# Main.net
KiCad netlist of a schematic drawn in EAGLE
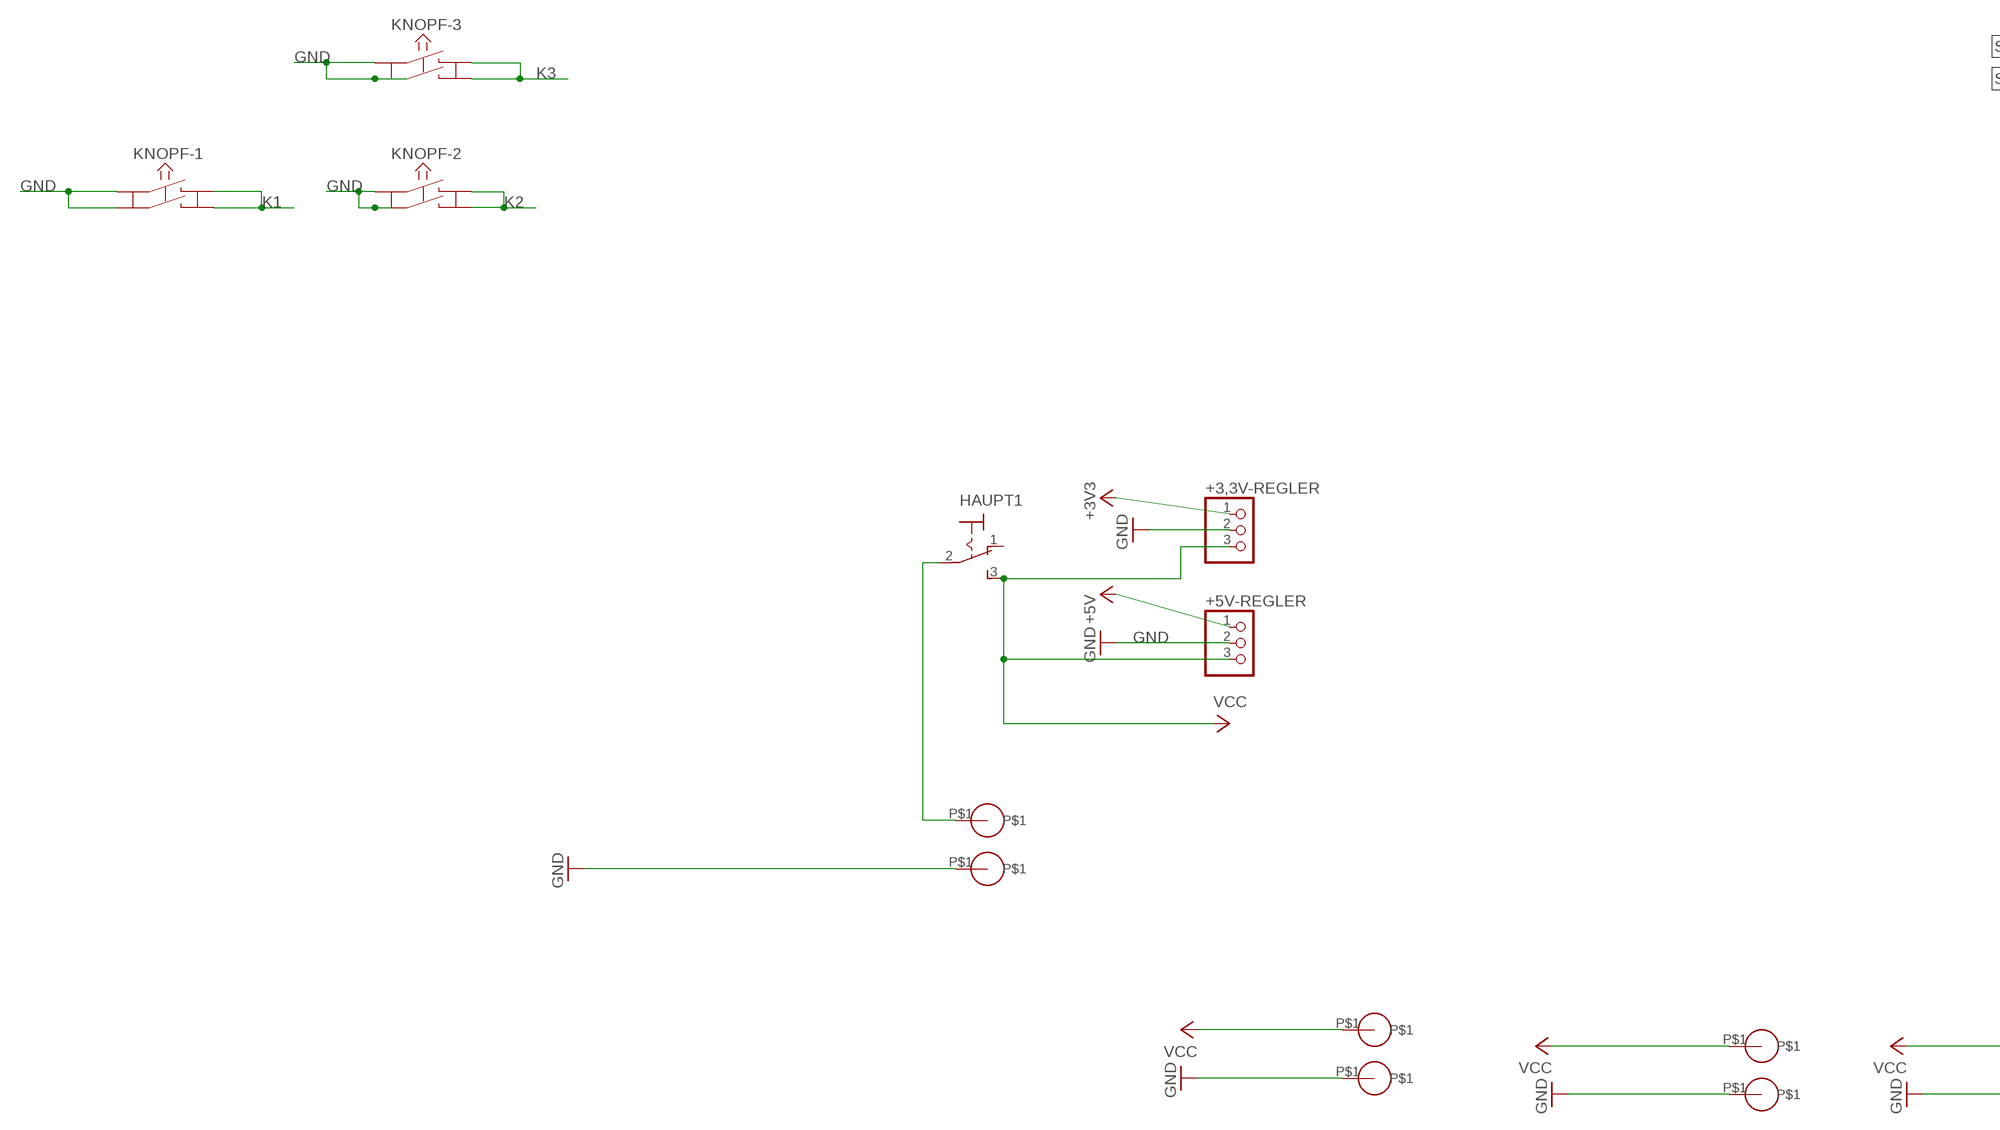
[diagram p0: schematic, sheet 1, part 1 of 3]
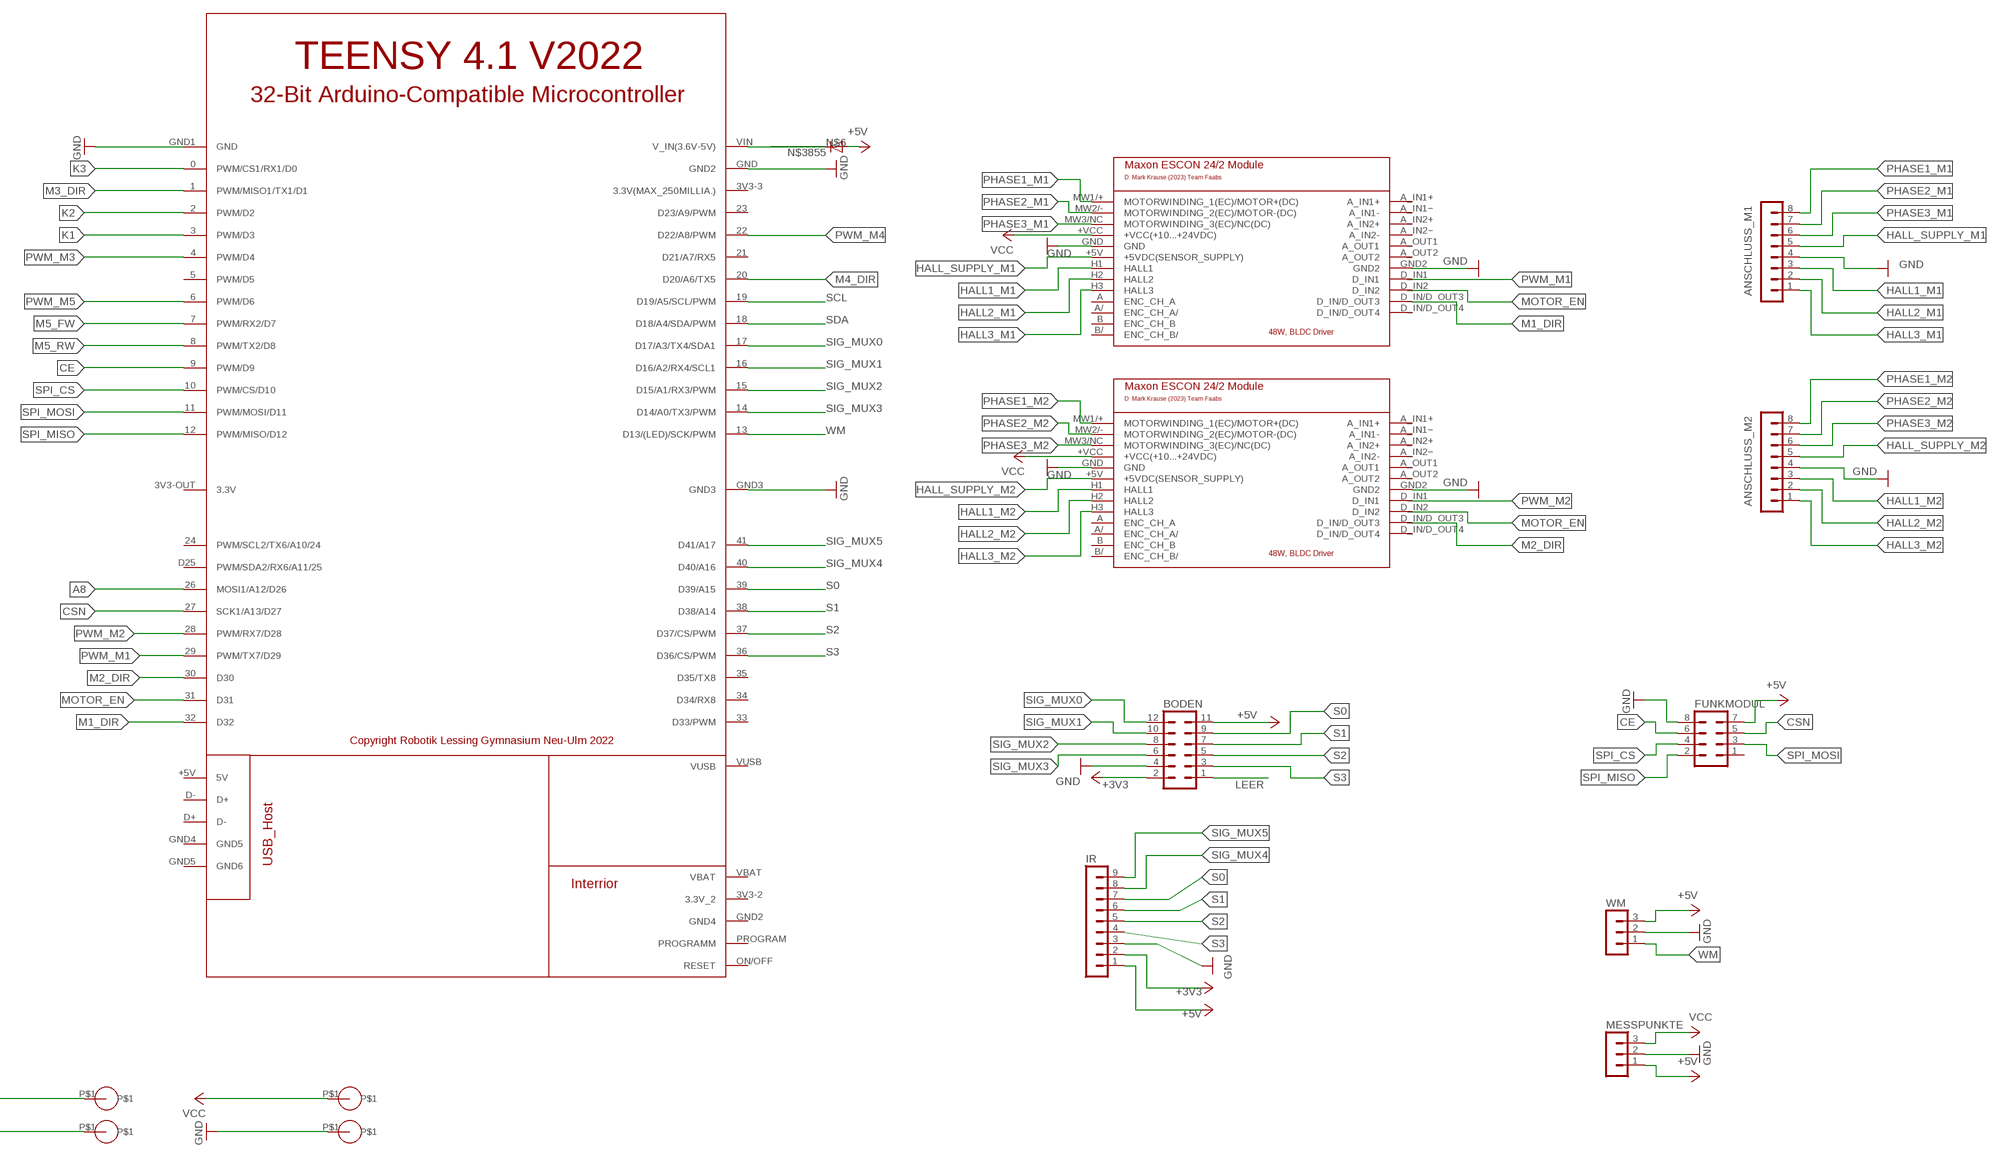
[diagram p1: schematic, sheet 1, part 2 of 3]
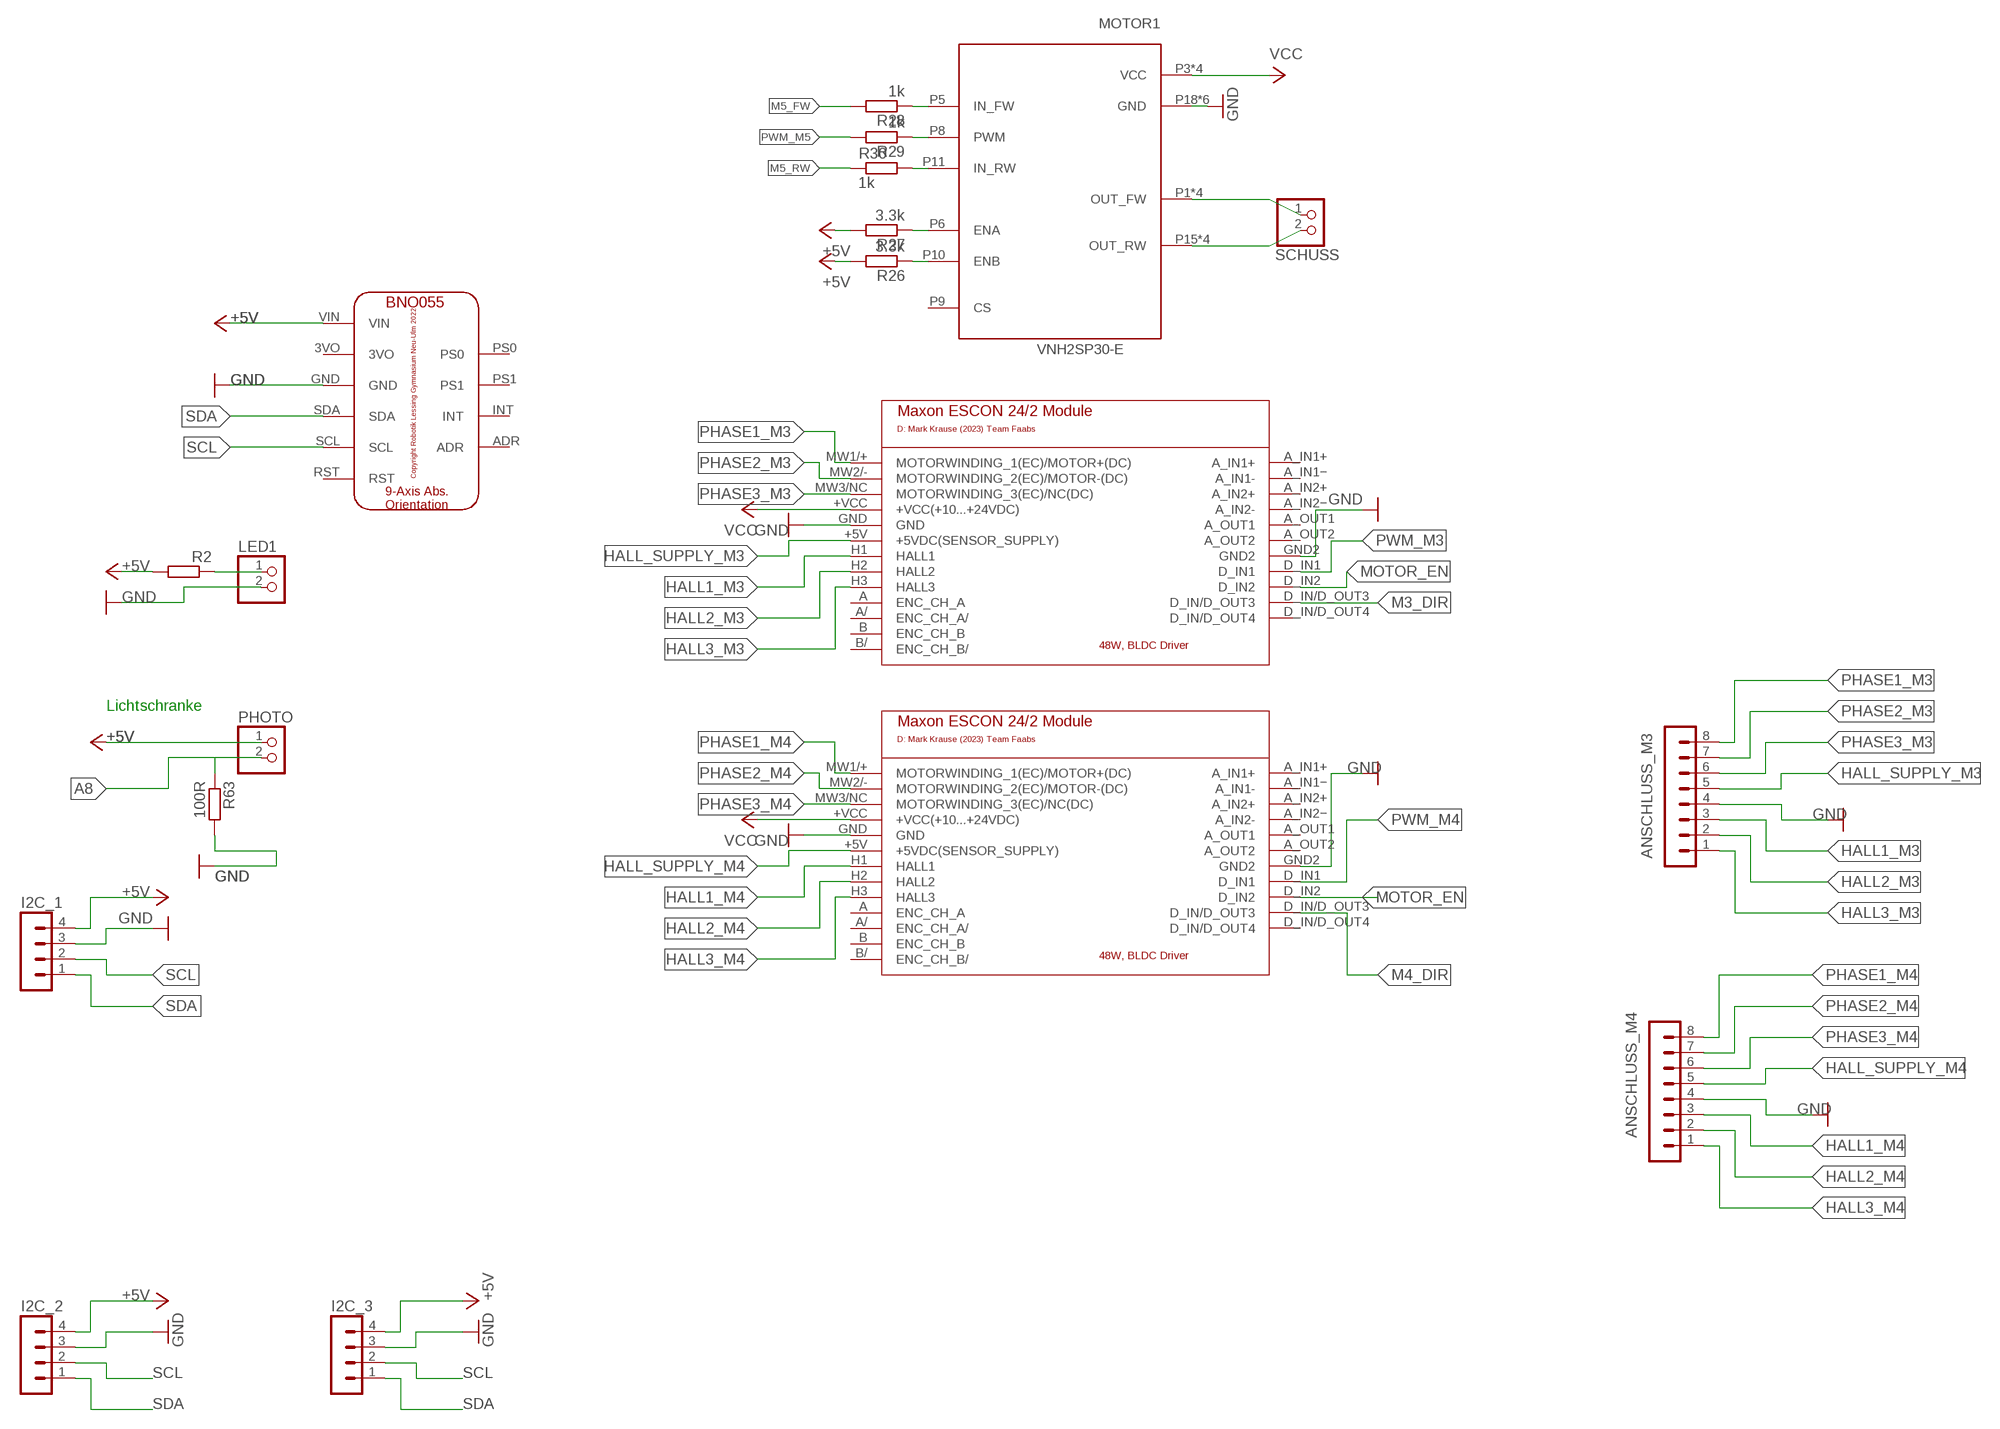
[diagram p2: schematic, sheet 1, part 3 of 3]

(export (version "E")
  (design (tool "Eeschema 10.0.6"))
  (components
    (comp (ref "+3,3V-REGLER")
      (value "PINHD-1X3")
      (footprint "eagle-import:1X03")
      (libsource (lib "eagle-import") (part "PINHD-1X3"))
    )
    (comp (ref "+5V-REGLER")
      (value "PINHD-1X3")
      (footprint "eagle-import:1X03")
      (libsource (lib "eagle-import") (part "PINHD-1X3"))
    )
    (comp (ref "ANSCHLUSS_M1")
      (value "MA08-1")
      (footprint "eagle-import:MA08-1")
      (libsource (lib "eagle-import") (part "MA08-1"))
    )
    (comp (ref "ANSCHLUSS_M2")
      (value "MA08-1")
      (footprint "eagle-import:MA08-1")
      (libsource (lib "eagle-import") (part "MA08-1"))
    )
    (comp (ref "ANSCHLUSS_M3")
      (value "MA08-1")
      (footprint "eagle-import:MA08-1")
      (libsource (lib "eagle-import") (part "MA08-1"))
    )
    (comp (ref "ANSCHLUSS_M4")
      (value "MA08-1")
      (footprint "eagle-import:MA08-1")
      (libsource (lib "eagle-import") (part "MA08-1"))
    )
    (comp (ref "BNO055")
      (value "BNO055")
      (footprint "eagle-import:BNO055")
      (libsource (lib "eagle-import") (part "BNO055"))
    )
    (comp (ref "BODEN")
      (value "MA06-2")
      (footprint "eagle-import:MA06-2")
      (libsource (lib "eagle-import") (part "MA06-2"))
    )
    (comp (ref "FUNKMODUL")
      (value "MA04-2")
      (footprint "eagle-import:MA04-2")
      (libsource (lib "eagle-import") (part "MA04-2"))
    )
    (comp (ref "GND")
      (value "PPAD")
      (footprint "eagle-import:PPAD")
      (libsource (lib "eagle-import") (part "PPAD"))
    )
    (comp (ref "GND10")
      (value "PPAD")
      (footprint "eagle-import:PPAD")
      (libsource (lib "eagle-import") (part "PPAD"))
    )
    (comp (ref "GND11")
      (value "PPAD")
      (footprint "eagle-import:PPAD")
      (libsource (lib "eagle-import") (part "PPAD"))
    )
    (comp (ref "GND35")
      (value "PPAD")
      (footprint "eagle-import:PPAD")
      (libsource (lib "eagle-import") (part "PPAD"))
    )
    (comp (ref "GND37")
      (value "PPAD")
      (footprint "eagle-import:PPAD")
      (libsource (lib "eagle-import") (part "PPAD"))
    )
    (comp (ref "HAUPT1")
      (value "320-916")
      (footprint "eagle-import:320-916")
      (libsource (lib "eagle-import") (part "320-916"))
    )
    (comp (ref "I2C_1")
      (value "MA04-1")
      (footprint "eagle-import:MA04-1")
      (libsource (lib "eagle-import") (part "MA04-1"))
    )
    (comp (ref "I2C_2")
      (value "MA04-1")
      (footprint "eagle-import:MA04-1")
      (libsource (lib "eagle-import") (part "MA04-1"))
    )
    (comp (ref "I2C_3")
      (value "MA04-1")
      (footprint "eagle-import:MA04-1")
      (libsource (lib "eagle-import") (part "MA04-1"))
    )
    (comp (ref "IR")
      (value "MA09-1")
      (footprint "eagle-import:MA09-1")
      (libsource (lib "eagle-import") (part "MA09-1"))
    )
    (comp (ref "KNOPF-1")
      (value "KSM611A")
      (footprint "eagle-import:KSM611A")
      (libsource (lib "eagle-import") (part "KSM611A"))
    )
    (comp (ref "KNOPF-2")
      (value "KSM611A")
      (footprint "eagle-import:KSM611A")
      (libsource (lib "eagle-import") (part "KSM611A"))
    )
    (comp (ref "KNOPF-3")
      (value "KSM611A")
      (footprint "eagle-import:KSM611A")
      (libsource (lib "eagle-import") (part "KSM611A"))
    )
    (comp (ref "LED1")
      (value "PINHD-1X2")
      (footprint "eagle-import:1X02")
      (libsource (lib "eagle-import") (part "PINHD-1X2"))
    )
    (comp (ref "MAIN")
      (value "PPAD")
      (footprint "eagle-import:PPAD")
      (libsource (lib "eagle-import") (part "PPAD"))
    )
    (comp (ref "MAIN1")
      (value "PPAD")
      (footprint "eagle-import:PPAD")
      (libsource (lib "eagle-import") (part "PPAD"))
    )
    (comp (ref "MAIN2")
      (value "PPAD")
      (footprint "eagle-import:PPAD")
      (libsource (lib "eagle-import") (part "PPAD"))
    )
    (comp (ref "MAIN3")
      (value "PPAD")
      (footprint "eagle-import:PPAD")
      (libsource (lib "eagle-import") (part "PPAD"))
    )
    (comp (ref "MAIN4")
      (value "PPAD")
      (footprint "eagle-import:PPAD")
      (libsource (lib "eagle-import") (part "PPAD"))
    )
    (comp (ref "MESSPUNKTE")
      (value "MA03-1")
      (footprint "eagle-import:MA03-1")
      (libsource (lib "eagle-import") (part "MA03-1"))
    )
    (comp (ref "MOTOR1")
      (value "VNH2SP30-E")
      (footprint "eagle-import:MP-SO-30")
      (libsource (lib "eagle-import") (part "VNH2SP30-E"))
    )
    (comp (ref "N$3855")
      (value "DIODE-SMB")
      (footprint "eagle-import:SMB")
      (libsource (lib "eagle-import") (part "DIODE-SMB"))
    )
    (comp (ref "PHOTO")
      (value "PINHD-1X2")
      (footprint "eagle-import:1X02")
      (libsource (lib "eagle-import") (part "PINHD-1X2"))
    )
    (comp (ref "R2")
      (value "100R")
      (footprint "eagle-import:R1206")
      (libsource (lib "eagle-import") (part "R-EU_R1206"))
    )
    (comp (ref "R26")
      (value "3.3k")
      (footprint "eagle-import:R0805")
      (libsource (lib "eagle-import") (part "R-EU_R0805"))
    )
    (comp (ref "R27")
      (value "3.3k")
      (footprint "eagle-import:R0805")
      (libsource (lib "eagle-import") (part "R-EU_R0805"))
    )
    (comp (ref "R28")
      (value "1k")
      (footprint "eagle-import:R0805")
      (libsource (lib "eagle-import") (part "R-EU_R0805"))
    )
    (comp (ref "R29")
      (value "1k")
      (footprint "eagle-import:R0805")
      (libsource (lib "eagle-import") (part "R-EU_R0805"))
    )
    (comp (ref "R30")
      (value "1k")
      (footprint "eagle-import:R0805")
      (libsource (lib "eagle-import") (part "R-EU_R0805"))
    )
    (comp (ref "R63")
      (value "100R")
      (footprint "eagle-import:R0805")
      (libsource (lib "eagle-import") (part "R-EU_R0805"))
    )
    (comp (ref "SCHUSS")
      (value "PINHD-1X2")
      (footprint "eagle-import:1X02")
      (libsource (lib "eagle-import") (part "PINHD-1X2"))
    )
    (comp (ref "U$1")
      (value "MAXON_ESCON24/2")
      (footprint "eagle-import:MAXON_ESCON24_2_MODULE")
      (libsource (lib "eagle-import") (part "MAXON_ESCON24/2"))
    )
    (comp (ref "U$2")
      (value "TEENSY_4.1")
      (footprint "eagle-import:TEENSY_4.1")
      (libsource (lib "eagle-import") (part "TEENSY_4.1"))
    )
    (comp (ref "U$3")
      (value "MAXON_ESCON24/2")
      (footprint "eagle-import:MAXON_ESCON24_2_MODULE")
      (libsource (lib "eagle-import") (part "MAXON_ESCON24/2"))
    )
    (comp (ref "U$4")
      (value "MAXON_ESCON24/2")
      (footprint "eagle-import:MAXON_ESCON24_2_MODULE")
      (libsource (lib "eagle-import") (part "MAXON_ESCON24/2"))
    )
    (comp (ref "U$5")
      (value "MAXON_ESCON24/2")
      (footprint "eagle-import:MAXON_ESCON24_2_MODULE")
      (libsource (lib "eagle-import") (part "MAXON_ESCON24/2"))
    )
    (comp (ref "WM")
      (value "MA03-1")
      (footprint "eagle-import:MA03-1")
      (libsource (lib "eagle-import") (part "MA03-1"))
    )
  )
  (nets
    (net (code "1") (name "+3V3") (class "Default")
      (node (ref "+3,3V-REGLER") (pin "1") (pinfunction "1_1") (pintype "passive"))
      (node (ref "BODEN") (pin "2") (pinfunction "2_2") (pintype "passive"))
      (node (ref "IR") (pin "2") (pinfunction "2_2") (pintype "passive"))
    )
    (net (code "2") (name "+5V") (class "Default")
      (node (ref "+5V-REGLER") (pin "1") (pinfunction "1_1") (pintype "passive"))
      (node (ref "BNO055") (pin "VIN") (pinfunction "VIN_VIN") (pintype "bidirectional"))
      (node (ref "BODEN") (pin "11") (pinfunction "11_11") (pintype "passive"))
      (node (ref "FUNKMODUL") (pin "7") (pinfunction "7_7") (pintype "passive"))
      (node (ref "I2C_1") (pin "4") (pinfunction "4_4") (pintype "passive"))
      (node (ref "I2C_2") (pin "4") (pinfunction "4_4") (pintype "passive"))
      (node (ref "I2C_3") (pin "4") (pinfunction "4_4") (pintype "passive"))
      (node (ref "IR") (pin "1") (pinfunction "1_1") (pintype "passive"))
      (node (ref "MESSPUNKTE") (pin "1") (pinfunction "1_1") (pintype "passive"))
      (node (ref "N$3855") (pin "A") (pinfunction "A_A") (pintype "passive"))
      (node (ref "PHOTO") (pin "1") (pinfunction "1_1") (pintype "passive"))
      (node (ref "R2") (pin "2") (pinfunction "2_2") (pintype "passive"))
      (node (ref "R26") (pin "2") (pinfunction "2_2") (pintype "passive"))
      (node (ref "R27") (pin "2") (pinfunction "2_2") (pintype "passive"))
      (node (ref "WM") (pin "3") (pinfunction "3_3") (pintype "passive"))
    )
    (net (code "3") (name "/LEER") (class "Default")
      (node (ref "BODEN") (pin "1") (pinfunction "1_1") (pintype "passive"))
    )
    (net (code "4") (name "/N$6") (class "Default")
      (node (ref "N$3855") (pin "C") (pinfunction "C_C") (pintype "passive"))
      (node (ref "U$2") (pin "VIN") (pinfunction "V_IN(3.6V-5V)_VIN") (pintype "bidirectional"))
    )
    (net (code "5") (name "A8") (class "Default")
      (node (ref "PHOTO") (pin "2") (pinfunction "2_2") (pintype "passive"))
      (node (ref "R63") (pin "1") (pinfunction "1_1") (pintype "passive"))
      (node (ref "U$2") (pin "26") (pinfunction "MOSI1/A12/D26_26") (pintype "bidirectional"))
    )
    (net (code "6") (name "CE") (class "Default")
      (node (ref "FUNKMODUL") (pin "6") (pinfunction "6_6") (pintype "passive"))
      (node (ref "U$2") (pin "9") (pinfunction "PWM/D9_9") (pintype "bidirectional"))
    )
    (net (code "7") (name "CSN") (class "Default")
      (node (ref "FUNKMODUL") (pin "5") (pinfunction "5_5") (pintype "passive"))
      (node (ref "U$2") (pin "27") (pinfunction "SCK1/A13/D27_27") (pintype "bidirectional"))
    )
    (net (code "8") (name "GND") (class "Default")
      (node (ref "+3,3V-REGLER") (pin "2") (pinfunction "2_2") (pintype "passive"))
      (node (ref "+5V-REGLER") (pin "2") (pinfunction "2_2") (pintype "passive"))
      (node (ref "ANSCHLUSS_M1") (pin "4") (pinfunction "4_4") (pintype "passive"))
      (node (ref "ANSCHLUSS_M2") (pin "4") (pinfunction "4_4") (pintype "passive"))
      (node (ref "ANSCHLUSS_M3") (pin "4") (pinfunction "4_4") (pintype "passive"))
      (node (ref "ANSCHLUSS_M4") (pin "4") (pinfunction "4_4") (pintype "passive"))
      (node (ref "BNO055") (pin "GND") (pinfunction "GND_GND") (pintype "bidirectional"))
      (node (ref "BODEN") (pin "4") (pinfunction "4_4") (pintype "passive"))
      (node (ref "FUNKMODUL") (pin "8") (pinfunction "8_8") (pintype "passive"))
      (node (ref "GND") (pin "P$1") (pinfunction "P$1_P$1") (pintype "bidirectional"))
      (node (ref "GND10") (pin "P$1") (pinfunction "P$1_P$1") (pintype "bidirectional"))
      (node (ref "GND11") (pin "P$1") (pinfunction "P$1_P$1") (pintype "bidirectional"))
      (node (ref "GND35") (pin "P$1") (pinfunction "P$1_P$1") (pintype "bidirectional"))
      (node (ref "GND37") (pin "P$1") (pinfunction "P$1_P$1") (pintype "bidirectional"))
      (node (ref "I2C_1") (pin "3") (pinfunction "3_3") (pintype "passive"))
      (node (ref "I2C_2") (pin "3") (pinfunction "3_3") (pintype "passive"))
      (node (ref "I2C_3") (pin "3") (pinfunction "3_3") (pintype "passive"))
      (node (ref "IR") (pin "3") (pinfunction "3_3") (pintype "passive"))
      (node (ref "KNOPF-1") (pin "A") (pinfunction "A_A") (pintype "passive"))
      (node (ref "KNOPF-1") (pin "C") (pinfunction "C_C") (pintype "passive"))
      (node (ref "KNOPF-2") (pin "A") (pinfunction "A_A") (pintype "passive"))
      (node (ref "KNOPF-2") (pin "C") (pinfunction "C_C") (pintype "passive"))
      (node (ref "KNOPF-3") (pin "A") (pinfunction "A_A") (pintype "passive"))
      (node (ref "KNOPF-3") (pin "C") (pinfunction "C_C") (pintype "passive"))
      (node (ref "LED1") (pin "2") (pinfunction "2_2") (pintype "passive"))
      (node (ref "MESSPUNKTE") (pin "2") (pinfunction "2_2") (pintype "passive"))
      (node (ref "MOTOR1") (pin "P18") (pinfunction "GND_P18") (pintype "power_in"))
      (node (ref "MOTOR1") (pin "P19") (pinfunction "GND_P19") (pintype "power_in"))
      (node (ref "MOTOR1") (pin "P20") (pinfunction "GND_P20") (pintype "power_in"))
      (node (ref "MOTOR1") (pin "P26") (pinfunction "GND_P26") (pintype "power_in"))
      (node (ref "MOTOR1") (pin "P27") (pinfunction "GND_P27") (pintype "power_in"))
      (node (ref "MOTOR1") (pin "P28") (pinfunction "GND_P28") (pintype "power_in"))
      (node (ref "R63") (pin "2") (pinfunction "2_2") (pintype "passive"))
      (node (ref "U$1") (pin "GND") (pinfunction "GND_GND") (pintype "power_in"))
      (node (ref "U$1") (pin "GND2") (pinfunction "GND2_GND2") (pintype "power_in"))
      (node (ref "U$2") (pin "GND") (pinfunction "GND2_GND") (pintype "bidirectional"))
      (node (ref "U$2") (pin "GND1") (pinfunction "GND_GND1") (pintype "bidirectional"))
      (node (ref "U$2") (pin "GND3") (pinfunction "GND3_GND3") (pintype "bidirectional"))
      (node (ref "U$3") (pin "GND") (pinfunction "GND_GND") (pintype "power_in"))
      (node (ref "U$3") (pin "GND2") (pinfunction "GND2_GND2") (pintype "power_in"))
      (node (ref "U$4") (pin "GND") (pinfunction "GND_GND") (pintype "power_in"))
      (node (ref "U$4") (pin "GND2") (pinfunction "GND2_GND2") (pintype "power_in"))
      (node (ref "U$5") (pin "GND") (pinfunction "GND_GND") (pintype "power_in"))
      (node (ref "U$5") (pin "GND2") (pinfunction "GND2_GND2") (pintype "power_in"))
      (node (ref "WM") (pin "2") (pinfunction "2_2") (pintype "passive"))
    )
    (net (code "9") (name "HALL1_M1") (class "Default")
      (node (ref "ANSCHLUSS_M1") (pin "3") (pinfunction "3_3") (pintype "passive"))
      (node (ref "U$1") (pin "H1") (pinfunction "HALL1_H1") (pintype "input"))
    )
    (net (code "10") (name "HALL1_M2") (class "Default")
      (node (ref "ANSCHLUSS_M2") (pin "3") (pinfunction "3_3") (pintype "passive"))
      (node (ref "U$3") (pin "H1") (pinfunction "HALL1_H1") (pintype "input"))
    )
    (net (code "11") (name "HALL1_M3") (class "Default")
      (node (ref "ANSCHLUSS_M3") (pin "3") (pinfunction "3_3") (pintype "passive"))
      (node (ref "U$4") (pin "H1") (pinfunction "HALL1_H1") (pintype "input"))
    )
    (net (code "12") (name "HALL1_M4") (class "Default")
      (node (ref "ANSCHLUSS_M4") (pin "3") (pinfunction "3_3") (pintype "passive"))
      (node (ref "U$5") (pin "H1") (pinfunction "HALL1_H1") (pintype "input"))
    )
    (net (code "13") (name "HALL2_M1") (class "Default")
      (node (ref "ANSCHLUSS_M1") (pin "2") (pinfunction "2_2") (pintype "passive"))
      (node (ref "U$1") (pin "H2") (pinfunction "HALL2_H2") (pintype "input"))
    )
    (net (code "14") (name "HALL2_M2") (class "Default")
      (node (ref "ANSCHLUSS_M2") (pin "2") (pinfunction "2_2") (pintype "passive"))
      (node (ref "U$3") (pin "H2") (pinfunction "HALL2_H2") (pintype "input"))
    )
    (net (code "15") (name "HALL2_M3") (class "Default")
      (node (ref "ANSCHLUSS_M3") (pin "2") (pinfunction "2_2") (pintype "passive"))
      (node (ref "U$4") (pin "H2") (pinfunction "HALL2_H2") (pintype "input"))
    )
    (net (code "16") (name "HALL2_M4") (class "Default")
      (node (ref "ANSCHLUSS_M4") (pin "2") (pinfunction "2_2") (pintype "passive"))
      (node (ref "U$5") (pin "H2") (pinfunction "HALL2_H2") (pintype "input"))
    )
    (net (code "17") (name "HALL3_M1") (class "Default")
      (node (ref "ANSCHLUSS_M1") (pin "1") (pinfunction "1_1") (pintype "passive"))
      (node (ref "U$1") (pin "H3") (pinfunction "HALL3_H3") (pintype "input"))
    )
    (net (code "18") (name "HALL3_M2") (class "Default")
      (node (ref "ANSCHLUSS_M2") (pin "1") (pinfunction "1_1") (pintype "passive"))
      (node (ref "U$3") (pin "H3") (pinfunction "HALL3_H3") (pintype "input"))
    )
    (net (code "19") (name "HALL3_M3") (class "Default")
      (node (ref "ANSCHLUSS_M3") (pin "1") (pinfunction "1_1") (pintype "passive"))
      (node (ref "U$4") (pin "H3") (pinfunction "HALL3_H3") (pintype "input"))
    )
    (net (code "20") (name "HALL3_M4") (class "Default")
      (node (ref "ANSCHLUSS_M4") (pin "1") (pinfunction "1_1") (pintype "passive"))
      (node (ref "U$5") (pin "H3") (pinfunction "HALL3_H3") (pintype "input"))
    )
    (net (code "21") (name "HALL_SUPPLY_M1") (class "Default")
      (node (ref "ANSCHLUSS_M1") (pin "5") (pinfunction "5_5") (pintype "passive"))
      (node (ref "U$1") (pin "+5V") (pinfunction "+5VDC(SENSOR_SUPPLY)_+5V") (pintype "output"))
    )
    (net (code "22") (name "HALL_SUPPLY_M2") (class "Default")
      (node (ref "ANSCHLUSS_M2") (pin "5") (pinfunction "5_5") (pintype "passive"))
      (node (ref "U$3") (pin "+5V") (pinfunction "+5VDC(SENSOR_SUPPLY)_+5V") (pintype "output"))
    )
    (net (code "23") (name "HALL_SUPPLY_M3") (class "Default")
      (node (ref "ANSCHLUSS_M3") (pin "5") (pinfunction "5_5") (pintype "passive"))
      (node (ref "U$4") (pin "+5V") (pinfunction "+5VDC(SENSOR_SUPPLY)_+5V") (pintype "output"))
    )
    (net (code "24") (name "HALL_SUPPLY_M4") (class "Default")
      (node (ref "ANSCHLUSS_M4") (pin "5") (pinfunction "5_5") (pintype "passive"))
      (node (ref "U$5") (pin "+5V") (pinfunction "+5VDC(SENSOR_SUPPLY)_+5V") (pintype "output"))
    )
    (net (code "25") (name "K1") (class "Default")
      (node (ref "KNOPF-1") (pin "B") (pinfunction "B_B") (pintype "passive"))
      (node (ref "KNOPF-1") (pin "D") (pinfunction "D_D") (pintype "passive"))
      (node (ref "U$2") (pin "3") (pinfunction "PWM/D3_3") (pintype "bidirectional"))
    )
    (net (code "26") (name "K2") (class "Default")
      (node (ref "KNOPF-2") (pin "B") (pinfunction "B_B") (pintype "passive"))
      (node (ref "KNOPF-2") (pin "D") (pinfunction "D_D") (pintype "passive"))
      (node (ref "U$2") (pin "2") (pinfunction "PWM/D2_2") (pintype "bidirectional"))
    )
    (net (code "27") (name "K3") (class "Default")
      (node (ref "KNOPF-3") (pin "B") (pinfunction "B_B") (pintype "passive"))
      (node (ref "KNOPF-3") (pin "D") (pinfunction "D_D") (pintype "passive"))
      (node (ref "U$2") (pin "0") (pinfunction "PWM/CS1/RX1/D0_0") (pintype "bidirectional"))
    )
    (net (code "28") (name "M1_DIR") (class "Default")
      (node (ref "U$1") (pin "D_IN/D_OUT3") (pinfunction "D_IN/D_OUT3_D_IN/D_OUT3") (pintype "bidirectional"))
      (node (ref "U$2") (pin "32") (pinfunction "D32_32") (pintype "bidirectional"))
    )
    (net (code "29") (name "M2_DIR") (class "Default")
      (node (ref "U$2") (pin "30") (pinfunction "D30_30") (pintype "bidirectional"))
      (node (ref "U$3") (pin "D_IN/D_OUT3") (pinfunction "D_IN/D_OUT3_D_IN/D_OUT3") (pintype "bidirectional"))
    )
    (net (code "30") (name "M3_DIR") (class "Default")
      (node (ref "U$2") (pin "1") (pinfunction "PWM/MISO1/TX1/D1_1") (pintype "bidirectional"))
      (node (ref "U$4") (pin "D_IN/D_OUT3") (pinfunction "D_IN/D_OUT3_D_IN/D_OUT3") (pintype "bidirectional"))
    )
    (net (code "31") (name "M4_DIR") (class "Default")
      (node (ref "U$2") (pin "20") (pinfunction "D20/A6/TX5_20") (pintype "bidirectional"))
      (node (ref "U$5") (pin "D_IN/D_OUT3") (pinfunction "D_IN/D_OUT3_D_IN/D_OUT3") (pintype "bidirectional"))
    )
    (net (code "32") (name "M5_FW") (class "Default")
      (node (ref "R28") (pin "2") (pinfunction "2_2") (pintype "passive"))
      (node (ref "U$2") (pin "7") (pinfunction "PWM/RX2/D7_7") (pintype "bidirectional"))
    )
    (net (code "33") (name "M5_RW") (class "Default")
      (node (ref "R30") (pin "1") (pinfunction "1_1") (pintype "passive"))
      (node (ref "U$2") (pin "8") (pinfunction "PWM/TX2/D8_8") (pintype "bidirectional"))
    )
    (net (code "34") (name "MOTOR_EN") (class "Default")
      (node (ref "U$1") (pin "D_IN2") (pinfunction "D_IN2_D_IN2") (pintype "input"))
      (node (ref "U$2") (pin "31") (pinfunction "D31_31") (pintype "bidirectional"))
      (node (ref "U$3") (pin "D_IN2") (pinfunction "D_IN2_D_IN2") (pintype "input"))
      (node (ref "U$4") (pin "D_IN2") (pinfunction "D_IN2_D_IN2") (pintype "input"))
      (node (ref "U$5") (pin "D_IN2") (pinfunction "D_IN2_D_IN2") (pintype "input"))
    )
    (net (code "35") (name "Net-(HAUPT1-P)") (class "Default")
      (node (ref "HAUPT1") (pin "2") (pinfunction "P_2") (pintype "passive"))
      (node (ref "MAIN") (pin "P$1") (pinfunction "P$1_P$1") (pintype "bidirectional"))
    )
    (net (code "36") (name "Net-(LED1-Pad1)") (class "Default")
      (node (ref "LED1") (pin "1") (pinfunction "1_1") (pintype "passive"))
      (node (ref "R2") (pin "1") (pinfunction "1_1") (pintype "passive"))
    )
    (net (code "37") (name "Net-(MOTOR1-ENA)") (class "Default")
      (node (ref "MOTOR1") (pin "P6") (pinfunction "ENA_P6") (pintype "input"))
      (node (ref "R27") (pin "1") (pinfunction "1_1") (pintype "passive"))
    )
    (net (code "38") (name "Net-(MOTOR1-ENB)") (class "Default")
      (node (ref "MOTOR1") (pin "P10") (pinfunction "ENB_P10") (pintype "input"))
      (node (ref "R26") (pin "1") (pinfunction "1_1") (pintype "passive"))
    )
    (net (code "39") (name "Net-(MOTOR1-IN_FW)") (class "Default")
      (node (ref "MOTOR1") (pin "P5") (pinfunction "IN_FW_P5") (pintype "input"))
      (node (ref "R28") (pin "1") (pinfunction "1_1") (pintype "passive"))
    )
    (net (code "40") (name "Net-(MOTOR1-IN_RW)") (class "Default")
      (node (ref "MOTOR1") (pin "P11") (pinfunction "IN_RW_P11") (pintype "input"))
      (node (ref "R30") (pin "2") (pinfunction "2_2") (pintype "passive"))
    )
    (net (code "41") (name "Net-(MOTOR1-OUT_FW-PadP1)") (class "Default")
      (node (ref "MOTOR1") (pin "P1") (pinfunction "OUT_FW_P1") (pintype "output"))
      (node (ref "MOTOR1") (pin "P25") (pinfunction "OUT_FW_P25") (pintype "output"))
      (node (ref "MOTOR1") (pin "P30") (pinfunction "OUT_FW_P30") (pintype "output"))
      (node (ref "MOTOR1") (pin "S2") (pinfunction "OUT_FW_S2") (pintype "output"))
      (node (ref "SCHUSS") (pin "1") (pinfunction "1_1") (pintype "passive"))
    )
    (net (code "42") (name "Net-(MOTOR1-OUT_RW-PadP15)") (class "Default")
      (node (ref "MOTOR1") (pin "P15") (pinfunction "OUT_RW_P15") (pintype "output"))
      (node (ref "MOTOR1") (pin "P16") (pinfunction "OUT_RW_P16") (pintype "output"))
      (node (ref "MOTOR1") (pin "P21") (pinfunction "OUT_RW_P21") (pintype "output"))
      (node (ref "MOTOR1") (pin "S3") (pinfunction "OUT_RW_S3") (pintype "output"))
      (node (ref "SCHUSS") (pin "2") (pinfunction "2_2") (pintype "passive"))
    )
    (net (code "43") (name "Net-(MOTOR1-PWM)") (class "Default")
      (node (ref "MOTOR1") (pin "P8") (pinfunction "PWM_P8") (pintype "input"))
      (node (ref "R29") (pin "1") (pinfunction "1_1") (pintype "passive"))
    )
    (net (code "44") (name "PHASE1_M1") (class "Default")
      (node (ref "ANSCHLUSS_M1") (pin "8") (pinfunction "8_8") (pintype "passive"))
      (node (ref "U$1") (pin "MW1/+") (pinfunction "MOTORWINDING_1(EC)/MOTOR+(DC)_MW1/+") (pintype "output"))
    )
    (net (code "45") (name "PHASE1_M2") (class "Default")
      (node (ref "ANSCHLUSS_M2") (pin "8") (pinfunction "8_8") (pintype "passive"))
      (node (ref "U$3") (pin "MW1/+") (pinfunction "MOTORWINDING_1(EC)/MOTOR+(DC)_MW1/+") (pintype "output"))
    )
    (net (code "46") (name "PHASE1_M3") (class "Default")
      (node (ref "ANSCHLUSS_M3") (pin "8") (pinfunction "8_8") (pintype "passive"))
      (node (ref "U$4") (pin "MW1/+") (pinfunction "MOTORWINDING_1(EC)/MOTOR+(DC)_MW1/+") (pintype "output"))
    )
    (net (code "47") (name "PHASE1_M4") (class "Default")
      (node (ref "ANSCHLUSS_M4") (pin "8") (pinfunction "8_8") (pintype "passive"))
      (node (ref "U$5") (pin "MW1/+") (pinfunction "MOTORWINDING_1(EC)/MOTOR+(DC)_MW1/+") (pintype "output"))
    )
    (net (code "48") (name "PHASE2_M1") (class "Default")
      (node (ref "ANSCHLUSS_M1") (pin "7") (pinfunction "7_7") (pintype "passive"))
      (node (ref "U$1") (pin "MW2/-") (pinfunction "MOTORWINDING_2(EC)/MOTOR-(DC)_MW2/-") (pintype "output"))
    )
    (net (code "49") (name "PHASE2_M2") (class "Default")
      (node (ref "ANSCHLUSS_M2") (pin "7") (pinfunction "7_7") (pintype "passive"))
      (node (ref "U$3") (pin "MW2/-") (pinfunction "MOTORWINDING_2(EC)/MOTOR-(DC)_MW2/-") (pintype "output"))
    )
    (net (code "50") (name "PHASE2_M3") (class "Default")
      (node (ref "ANSCHLUSS_M3") (pin "7") (pinfunction "7_7") (pintype "passive"))
      (node (ref "U$4") (pin "MW2/-") (pinfunction "MOTORWINDING_2(EC)/MOTOR-(DC)_MW2/-") (pintype "output"))
    )
    (net (code "51") (name "PHASE2_M4") (class "Default")
      (node (ref "ANSCHLUSS_M4") (pin "7") (pinfunction "7_7") (pintype "passive"))
      (node (ref "U$5") (pin "MW2/-") (pinfunction "MOTORWINDING_2(EC)/MOTOR-(DC)_MW2/-") (pintype "output"))
    )
    (net (code "52") (name "PHASE3_M1") (class "Default")
      (node (ref "ANSCHLUSS_M1") (pin "6") (pinfunction "6_6") (pintype "passive"))
      (node (ref "U$1") (pin "MW3/NC") (pinfunction "MOTORWINDING_3(EC)/NC(DC)_MW3/NC") (pintype "output"))
    )
    (net (code "53") (name "PHASE3_M2") (class "Default")
      (node (ref "ANSCHLUSS_M2") (pin "6") (pinfunction "6_6") (pintype "passive"))
      (node (ref "U$3") (pin "MW3/NC") (pinfunction "MOTORWINDING_3(EC)/NC(DC)_MW3/NC") (pintype "output"))
    )
    (net (code "54") (name "PHASE3_M3") (class "Default")
      (node (ref "ANSCHLUSS_M3") (pin "6") (pinfunction "6_6") (pintype "passive"))
      (node (ref "U$4") (pin "MW3/NC") (pinfunction "MOTORWINDING_3(EC)/NC(DC)_MW3/NC") (pintype "output"))
    )
    (net (code "55") (name "PHASE3_M4") (class "Default")
      (node (ref "ANSCHLUSS_M4") (pin "6") (pinfunction "6_6") (pintype "passive"))
      (node (ref "U$5") (pin "MW3/NC") (pinfunction "MOTORWINDING_3(EC)/NC(DC)_MW3/NC") (pintype "output"))
    )
    (net (code "56") (name "PWM_M1") (class "Default")
      (node (ref "U$1") (pin "D_IN1") (pinfunction "D_IN1_D_IN1") (pintype "input"))
      (node (ref "U$2") (pin "29") (pinfunction "PWM/TX7/D29_29") (pintype "bidirectional"))
    )
    (net (code "57") (name "PWM_M2") (class "Default")
      (node (ref "U$2") (pin "28") (pinfunction "PWM/RX7/D28_28") (pintype "bidirectional"))
      (node (ref "U$3") (pin "D_IN1") (pinfunction "D_IN1_D_IN1") (pintype "input"))
    )
    (net (code "58") (name "PWM_M3") (class "Default")
      (node (ref "U$2") (pin "4") (pinfunction "PWM/D4_4") (pintype "bidirectional"))
      (node (ref "U$4") (pin "D_IN1") (pinfunction "D_IN1_D_IN1") (pintype "input"))
    )
    (net (code "59") (name "PWM_M4") (class "Default")
      (node (ref "U$2") (pin "22") (pinfunction "D22/A8/PWM_22") (pintype "bidirectional"))
      (node (ref "U$5") (pin "D_IN1") (pinfunction "D_IN1_D_IN1") (pintype "input"))
    )
    (net (code "60") (name "PWM_M5") (class "Default")
      (node (ref "R29") (pin "2") (pinfunction "2_2") (pintype "passive"))
      (node (ref "U$2") (pin "6") (pinfunction "PWM/D6_6") (pintype "bidirectional"))
    )
    (net (code "61") (name "S0") (class "Default")
      (node (ref "BODEN") (pin "9") (pinfunction "9_9") (pintype "passive"))
      (node (ref "IR") (pin "7") (pinfunction "7_7") (pintype "passive"))
      (node (ref "U$2") (pin "39") (pinfunction "D39/A15_39") (pintype "bidirectional"))
    )
    (net (code "62") (name "S1") (class "Default")
      (node (ref "BODEN") (pin "7") (pinfunction "7_7") (pintype "passive"))
      (node (ref "IR") (pin "6") (pinfunction "6_6") (pintype "passive"))
      (node (ref "U$2") (pin "38") (pinfunction "D38/A14_38") (pintype "bidirectional"))
    )
    (net (code "63") (name "S2") (class "Default")
      (node (ref "BODEN") (pin "5") (pinfunction "5_5") (pintype "passive"))
      (node (ref "IR") (pin "5") (pinfunction "5_5") (pintype "passive"))
      (node (ref "U$2") (pin "37") (pinfunction "D37/CS/PWM_37") (pintype "bidirectional"))
    )
    (net (code "64") (name "S3") (class "Default")
      (node (ref "BODEN") (pin "3") (pinfunction "3_3") (pintype "passive"))
      (node (ref "IR") (pin "4") (pinfunction "4_4") (pintype "passive"))
      (node (ref "U$2") (pin "36") (pinfunction "D36/CS/PWM_36") (pintype "bidirectional"))
    )
    (net (code "65") (name "SCL") (class "Default")
      (node (ref "BNO055") (pin "SCL") (pinfunction "SCL_SCL") (pintype "bidirectional"))
      (node (ref "I2C_1") (pin "2") (pinfunction "2_2") (pintype "passive"))
      (node (ref "I2C_2") (pin "2") (pinfunction "2_2") (pintype "passive"))
      (node (ref "I2C_3") (pin "2") (pinfunction "2_2") (pintype "passive"))
      (node (ref "U$2") (pin "19") (pinfunction "D19/A5/SCL/PWM_19") (pintype "bidirectional"))
    )
    (net (code "66") (name "SDA") (class "Default")
      (node (ref "BNO055") (pin "SDA") (pinfunction "SDA_SDA") (pintype "bidirectional"))
      (node (ref "I2C_1") (pin "1") (pinfunction "1_1") (pintype "passive"))
      (node (ref "I2C_2") (pin "1") (pinfunction "1_1") (pintype "passive"))
      (node (ref "I2C_3") (pin "1") (pinfunction "1_1") (pintype "passive"))
      (node (ref "U$2") (pin "18") (pinfunction "D18/A4/SDA/PWM_18") (pintype "bidirectional"))
    )
    (net (code "67") (name "SIG_MUX0") (class "Default")
      (node (ref "BODEN") (pin "12") (pinfunction "12_12") (pintype "passive"))
      (node (ref "U$2") (pin "17") (pinfunction "D17/A3/TX4/SDA1_17") (pintype "bidirectional"))
    )
    (net (code "68") (name "SIG_MUX1") (class "Default")
      (node (ref "BODEN") (pin "10") (pinfunction "10_10") (pintype "passive"))
      (node (ref "U$2") (pin "16") (pinfunction "D16/A2/RX4/SCL1_16") (pintype "bidirectional"))
    )
    (net (code "69") (name "SIG_MUX2") (class "Default")
      (node (ref "BODEN") (pin "8") (pinfunction "8_8") (pintype "passive"))
      (node (ref "U$2") (pin "15") (pinfunction "D15/A1/RX3/PWM_15") (pintype "bidirectional"))
    )
    (net (code "70") (name "SIG_MUX3") (class "Default")
      (node (ref "BODEN") (pin "6") (pinfunction "6_6") (pintype "passive"))
      (node (ref "U$2") (pin "14") (pinfunction "D14/A0/TX3/PWM_14") (pintype "bidirectional"))
    )
    (net (code "71") (name "SIG_MUX4") (class "Default")
      (node (ref "IR") (pin "8") (pinfunction "8_8") (pintype "passive"))
      (node (ref "U$2") (pin "40") (pinfunction "D40/A16_40") (pintype "bidirectional"))
    )
    (net (code "72") (name "SIG_MUX5") (class "Default")
      (node (ref "IR") (pin "9") (pinfunction "9_9") (pintype "passive"))
      (node (ref "U$2") (pin "41") (pinfunction "D41/A17_41") (pintype "bidirectional"))
    )
    (net (code "73") (name "SPI_CS") (class "Default")
      (node (ref "FUNKMODUL") (pin "4") (pinfunction "4_4") (pintype "passive"))
      (node (ref "U$2") (pin "10") (pinfunction "PWM/CS/D10_10") (pintype "bidirectional"))
    )
    (net (code "74") (name "SPI_MISO") (class "Default")
      (node (ref "FUNKMODUL") (pin "2") (pinfunction "2_2") (pintype "passive"))
      (node (ref "U$2") (pin "12") (pinfunction "PWM/MISO/D12_12") (pintype "bidirectional"))
    )
    (net (code "75") (name "SPI_MOSI") (class "Default")
      (node (ref "FUNKMODUL") (pin "3") (pinfunction "3_3") (pintype "passive"))
      (node (ref "U$2") (pin "11") (pinfunction "PWM/MOSI/D11_11") (pintype "bidirectional"))
    )
    (net (code "76") (name "VCC") (class "Default")
      (node (ref "+3,3V-REGLER") (pin "3") (pinfunction "3_3") (pintype "passive"))
      (node (ref "+5V-REGLER") (pin "3") (pinfunction "3_3") (pintype "passive"))
      (node (ref "HAUPT1") (pin "3") (pinfunction "S_3") (pintype "passive"))
      (node (ref "MAIN1") (pin "P$1") (pinfunction "P$1_P$1") (pintype "bidirectional"))
      (node (ref "MAIN2") (pin "P$1") (pinfunction "P$1_P$1") (pintype "bidirectional"))
      (node (ref "MAIN3") (pin "P$1") (pinfunction "P$1_P$1") (pintype "bidirectional"))
      (node (ref "MAIN4") (pin "P$1") (pinfunction "P$1_P$1") (pintype "bidirectional"))
      (node (ref "MESSPUNKTE") (pin "3") (pinfunction "3_3") (pintype "passive"))
      (node (ref "MOTOR1") (pin "P13") (pinfunction "VCC_P13") (pintype "power_in"))
      (node (ref "MOTOR1") (pin "P23") (pinfunction "VCC_P23") (pintype "power_in"))
      (node (ref "MOTOR1") (pin "P3") (pinfunction "VCC_P3") (pintype "power_in"))
      (node (ref "MOTOR1") (pin "S1") (pinfunction "VCC_S1") (pintype "power_in"))
      (node (ref "U$1") (pin "+VCC") (pinfunction "+VCC(+10...+24VDC)_+VCC") (pintype "power_in"))
      (node (ref "U$3") (pin "+VCC") (pinfunction "+VCC(+10...+24VDC)_+VCC") (pintype "power_in"))
      (node (ref "U$4") (pin "+VCC") (pinfunction "+VCC(+10...+24VDC)_+VCC") (pintype "power_in"))
      (node (ref "U$5") (pin "+VCC") (pinfunction "+VCC(+10...+24VDC)_+VCC") (pintype "power_in"))
    )
    (net (code "77") (name "WM") (class "Default")
      (node (ref "U$2") (pin "13") (pinfunction "D13/(LED)/SCK/PWM_13") (pintype "bidirectional"))
      (node (ref "WM") (pin "1") (pinfunction "1_1") (pintype "passive"))
    )
    (net (code "78") (name "unconnected-(BNO055-Pad3VO)") (class "Default")
      (node (ref "BNO055") (pin "3VO") (pinfunction "3VO_3VO") (pintype "bidirectional"))
    )
    (net (code "79") (name "unconnected-(BNO055-PadADR)") (class "Default")
      (node (ref "BNO055") (pin "ADR") (pinfunction "ADR_ADR") (pintype "bidirectional"))
    )
    (net (code "80") (name "unconnected-(BNO055-PadINT)") (class "Default")
      (node (ref "BNO055") (pin "INT") (pinfunction "INT_INT") (pintype "bidirectional"))
    )
    (net (code "81") (name "unconnected-(BNO055-PadPS0)") (class "Default")
      (node (ref "BNO055") (pin "PS0") (pinfunction "PS0_PS0") (pintype "bidirectional"))
    )
    (net (code "82") (name "unconnected-(BNO055-PadPS1)") (class "Default")
      (node (ref "BNO055") (pin "PS1") (pinfunction "PS1_PS1") (pintype "bidirectional"))
    )
    (net (code "83") (name "unconnected-(BNO055-PadRST)") (class "Default")
      (node (ref "BNO055") (pin "RST") (pinfunction "RST_RST") (pintype "bidirectional"))
    )
    (net (code "84") (name "unconnected-(FUNKMODUL-Pad1)") (class "Default")
      (node (ref "FUNKMODUL") (pin "1") (pinfunction "1_1") (pintype "passive"))
    )
    (net (code "85") (name "unconnected-(HAUPT1-O-Pad1)") (class "Default")
      (node (ref "HAUPT1") (pin "1") (pinfunction "O_1") (pintype "passive"))
    )
    (net (code "86") (name "unconnected-(MOTOR1-CS-PadP9)") (class "Default")
      (node (ref "MOTOR1") (pin "P9") (pinfunction "CS_P9") (pintype "input"))
    )
    (net (code "87") (name "unconnected-(U$1-A_IN1--PadA_IN1−)") (class "Default")
      (node (ref "U$1") (pin "A_IN1−") (pinfunction "A_IN1-_A_IN1−") (pintype "input"))
    )
    (net (code "88") (name "unconnected-(U$1-A_IN2--PadA_IN2−)") (class "Default")
      (node (ref "U$1") (pin "A_IN2−") (pinfunction "A_IN2-_A_IN2−") (pintype "input"))
    )
    (net (code "89") (name "unconnected-(U$1-ENC_CH_A-PadA)") (class "Default")
      (node (ref "U$1") (pin "A") (pinfunction "ENC_CH_A_A") (pintype "input"))
    )
    (net (code "90") (name "unconnected-(U$1-ENC_CH_A{slash}-PadA{slash})") (class "Default")
      (node (ref "U$1") (pin "A/") (pinfunction "ENC_CH_A/_A/") (pintype "input"))
    )
    (net (code "91") (name "unconnected-(U$1-ENC_CH_B-PadB)") (class "Default")
      (node (ref "U$1") (pin "B") (pinfunction "ENC_CH_B_B") (pintype "input"))
    )
    (net (code "92") (name "unconnected-(U$1-ENC_CH_B{slash}-PadB{slash})") (class "Default")
      (node (ref "U$1") (pin "B/") (pinfunction "ENC_CH_B/_B/") (pintype "input"))
    )
    (net (code "93") (name "unconnected-(U$1-PadA_IN1+)") (class "Default")
      (node (ref "U$1") (pin "A_IN1+") (pinfunction "A_IN1+_A_IN1+") (pintype "input"))
    )
    (net (code "94") (name "unconnected-(U$1-PadA_IN2+)") (class "Default")
      (node (ref "U$1") (pin "A_IN2+") (pinfunction "A_IN2+_A_IN2+") (pintype "input"))
    )
    (net (code "95") (name "unconnected-(U$1-PadA_OUT1)") (class "Default")
      (node (ref "U$1") (pin "A_OUT1") (pinfunction "A_OUT1_A_OUT1") (pintype "output"))
    )
    (net (code "96") (name "unconnected-(U$1-PadA_OUT2)") (class "Default")
      (node (ref "U$1") (pin "A_OUT2") (pinfunction "A_OUT2_A_OUT2") (pintype "output"))
    )
    (net (code "97") (name "unconnected-(U$1-PadD_IN{slash}D_OUT4)") (class "Default")
      (node (ref "U$1") (pin "D_IN/D_OUT4") (pinfunction "D_IN/D_OUT4_D_IN/D_OUT4") (pintype "bidirectional"))
    )
    (net (code "98") (name "unconnected-(U$2-3.3V(MAX_250MILLIA.)-Pad3V3-3)") (class "Default")
      (node (ref "U$2") (pin "3V3-3") (pinfunction "3.3V(MAX_250MILLIA.)_3V3-3") (pintype "bidirectional"))
    )
    (net (code "99") (name "unconnected-(U$2-3.3V-Pad3V3-OUT)") (class "Default")
      (node (ref "U$2") (pin "3V3-OUT") (pinfunction "3.3V_3V3-OUT") (pintype "bidirectional"))
    )
    (net (code "100") (name "unconnected-(U$2-3.3V_2-Pad3V3-2)") (class "Default")
      (node (ref "U$2") (pin "3V3-2") (pinfunction "3.3V_2_3V3-2") (pintype "bidirectional"))
    )
    (net (code "101") (name "unconnected-(U$2-5V-Pad+5V)") (class "Default")
      (node (ref "U$2") (pin "+5V") (pinfunction "5V_+5V") (pintype "bidirectional"))
    )
    (net (code "102") (name "unconnected-(U$2-D+-PadD-)") (class "Default")
      (node (ref "U$2") (pin "D-") (pinfunction "D+_D-") (pintype "bidirectional"))
    )
    (net (code "103") (name "unconnected-(U$2-D--PadD+)") (class "Default")
      (node (ref "U$2") (pin "D+") (pinfunction "D-_D+") (pintype "bidirectional"))
    )
    (net (code "104") (name "unconnected-(U$2-D21{slash}A7{slash}RX5-Pad21)") (class "Default")
      (node (ref "U$2") (pin "21") (pinfunction "D21/A7/RX5_21") (pintype "bidirectional"))
    )
    (net (code "105") (name "unconnected-(U$2-D23{slash}A9{slash}PWM-Pad23)") (class "Default")
      (node (ref "U$2") (pin "23") (pinfunction "D23/A9/PWM_23") (pintype "bidirectional"))
    )
    (net (code "106") (name "unconnected-(U$2-D33{slash}PWM-Pad33)") (class "Default")
      (node (ref "U$2") (pin "33") (pinfunction "D33/PWM_33") (pintype "bidirectional"))
    )
    (net (code "107") (name "unconnected-(U$2-D34{slash}RX8-Pad34)") (class "Default")
      (node (ref "U$2") (pin "34") (pinfunction "D34/RX8_34") (pintype "bidirectional"))
    )
    (net (code "108") (name "unconnected-(U$2-D35{slash}TX8-Pad35)") (class "Default")
      (node (ref "U$2") (pin "35") (pinfunction "D35/TX8_35") (pintype "bidirectional"))
    )
    (net (code "109") (name "unconnected-(U$2-GND4-PadGND2)") (class "Default")
      (node (ref "U$2") (pin "GND2") (pinfunction "GND4_GND2") (pintype "bidirectional"))
    )
    (net (code "110") (name "unconnected-(U$2-GND5-PadGND4)") (class "Default")
      (node (ref "U$2") (pin "GND4") (pinfunction "GND5_GND4") (pintype "bidirectional"))
    )
    (net (code "111") (name "unconnected-(U$2-GND6-PadGND5)") (class "Default")
      (node (ref "U$2") (pin "GND5") (pinfunction "GND6_GND5") (pintype "bidirectional"))
    )
    (net (code "112") (name "unconnected-(U$2-PROGRAMM-PadPROGRAM)") (class "Default")
      (node (ref "U$2") (pin "PROGRAM") (pinfunction "PROGRAMM_PROGRAM") (pintype "bidirectional"))
    )
    (net (code "113") (name "unconnected-(U$2-PWM{slash}D5-Pad5)") (class "Default")
      (node (ref "U$2") (pin "5") (pinfunction "PWM/D5_5") (pintype "bidirectional"))
    )
    (net (code "114") (name "unconnected-(U$2-PWM{slash}SCL2{slash}TX6{slash}A10{slash}24-Pad24)") (class "Default")
      (node (ref "U$2") (pin "24") (pinfunction "PWM/SCL2/TX6/A10/24_24") (pintype "bidirectional"))
    )
    (net (code "115") (name "unconnected-(U$2-PWM{slash}SDA2{slash}RX6{slash}A11{slash}25-PadD25)") (class "Default")
      (node (ref "U$2") (pin "D25") (pinfunction "PWM/SDA2/RX6/A11/25_D25") (pintype "bidirectional"))
    )
    (net (code "116") (name "unconnected-(U$2-PadVBAT)") (class "Default")
      (node (ref "U$2") (pin "VBAT") (pinfunction "VBAT_VBAT") (pintype "bidirectional"))
    )
    (net (code "117") (name "unconnected-(U$2-PadVUSB)") (class "Default")
      (node (ref "U$2") (pin "VUSB") (pinfunction "VUSB_VUSB") (pintype "bidirectional"))
    )
    (net (code "118") (name "unconnected-(U$2-RESET-PadON{slash}OFF)") (class "Default")
      (node (ref "U$2") (pin "ON/OFF") (pinfunction "RESET_ON/OFF") (pintype "bidirectional"))
    )
    (net (code "119") (name "unconnected-(U$3-A_IN1--PadA_IN1−)") (class "Default")
      (node (ref "U$3") (pin "A_IN1−") (pinfunction "A_IN1-_A_IN1−") (pintype "input"))
    )
    (net (code "120") (name "unconnected-(U$3-A_IN2--PadA_IN2−)") (class "Default")
      (node (ref "U$3") (pin "A_IN2−") (pinfunction "A_IN2-_A_IN2−") (pintype "input"))
    )
    (net (code "121") (name "unconnected-(U$3-ENC_CH_A-PadA)") (class "Default")
      (node (ref "U$3") (pin "A") (pinfunction "ENC_CH_A_A") (pintype "input"))
    )
    (net (code "122") (name "unconnected-(U$3-ENC_CH_A{slash}-PadA{slash})") (class "Default")
      (node (ref "U$3") (pin "A/") (pinfunction "ENC_CH_A/_A/") (pintype "input"))
    )
    (net (code "123") (name "unconnected-(U$3-ENC_CH_B-PadB)") (class "Default")
      (node (ref "U$3") (pin "B") (pinfunction "ENC_CH_B_B") (pintype "input"))
    )
    (net (code "124") (name "unconnected-(U$3-ENC_CH_B{slash}-PadB{slash})") (class "Default")
      (node (ref "U$3") (pin "B/") (pinfunction "ENC_CH_B/_B/") (pintype "input"))
    )
    (net (code "125") (name "unconnected-(U$3-PadA_IN1+)") (class "Default")
      (node (ref "U$3") (pin "A_IN1+") (pinfunction "A_IN1+_A_IN1+") (pintype "input"))
    )
    (net (code "126") (name "unconnected-(U$3-PadA_IN2+)") (class "Default")
      (node (ref "U$3") (pin "A_IN2+") (pinfunction "A_IN2+_A_IN2+") (pintype "input"))
    )
    (net (code "127") (name "unconnected-(U$3-PadA_OUT1)") (class "Default")
      (node (ref "U$3") (pin "A_OUT1") (pinfunction "A_OUT1_A_OUT1") (pintype "output"))
    )
    (net (code "128") (name "unconnected-(U$3-PadA_OUT2)") (class "Default")
      (node (ref "U$3") (pin "A_OUT2") (pinfunction "A_OUT2_A_OUT2") (pintype "output"))
    )
    (net (code "129") (name "unconnected-(U$3-PadD_IN{slash}D_OUT4)") (class "Default")
      (node (ref "U$3") (pin "D_IN/D_OUT4") (pinfunction "D_IN/D_OUT4_D_IN/D_OUT4") (pintype "bidirectional"))
    )
    (net (code "130") (name "unconnected-(U$4-A_IN1--PadA_IN1−)") (class "Default")
      (node (ref "U$4") (pin "A_IN1−") (pinfunction "A_IN1-_A_IN1−") (pintype "input"))
    )
    (net (code "131") (name "unconnected-(U$4-A_IN2--PadA_IN2−)") (class "Default")
      (node (ref "U$4") (pin "A_IN2−") (pinfunction "A_IN2-_A_IN2−") (pintype "input"))
    )
    (net (code "132") (name "unconnected-(U$4-ENC_CH_A-PadA)") (class "Default")
      (node (ref "U$4") (pin "A") (pinfunction "ENC_CH_A_A") (pintype "input"))
    )
    (net (code "133") (name "unconnected-(U$4-ENC_CH_A{slash}-PadA{slash})") (class "Default")
      (node (ref "U$4") (pin "A/") (pinfunction "ENC_CH_A/_A/") (pintype "input"))
    )
    (net (code "134") (name "unconnected-(U$4-ENC_CH_B-PadB)") (class "Default")
      (node (ref "U$4") (pin "B") (pinfunction "ENC_CH_B_B") (pintype "input"))
    )
    (net (code "135") (name "unconnected-(U$4-ENC_CH_B{slash}-PadB{slash})") (class "Default")
      (node (ref "U$4") (pin "B/") (pinfunction "ENC_CH_B/_B/") (pintype "input"))
    )
    (net (code "136") (name "unconnected-(U$4-PadA_IN1+)") (class "Default")
      (node (ref "U$4") (pin "A_IN1+") (pinfunction "A_IN1+_A_IN1+") (pintype "input"))
    )
    (net (code "137") (name "unconnected-(U$4-PadA_IN2+)") (class "Default")
      (node (ref "U$4") (pin "A_IN2+") (pinfunction "A_IN2+_A_IN2+") (pintype "input"))
    )
    (net (code "138") (name "unconnected-(U$4-PadA_OUT1)") (class "Default")
      (node (ref "U$4") (pin "A_OUT1") (pinfunction "A_OUT1_A_OUT1") (pintype "output"))
    )
    (net (code "139") (name "unconnected-(U$4-PadA_OUT2)") (class "Default")
      (node (ref "U$4") (pin "A_OUT2") (pinfunction "A_OUT2_A_OUT2") (pintype "output"))
    )
    (net (code "140") (name "unconnected-(U$4-PadD_IN{slash}D_OUT4)") (class "Default")
      (node (ref "U$4") (pin "D_IN/D_OUT4") (pinfunction "D_IN/D_OUT4_D_IN/D_OUT4") (pintype "bidirectional"))
    )
    (net (code "141") (name "unconnected-(U$5-A_IN1--PadA_IN1−)") (class "Default")
      (node (ref "U$5") (pin "A_IN1−") (pinfunction "A_IN1-_A_IN1−") (pintype "input"))
    )
    (net (code "142") (name "unconnected-(U$5-A_IN2--PadA_IN2−)") (class "Default")
      (node (ref "U$5") (pin "A_IN2−") (pinfunction "A_IN2-_A_IN2−") (pintype "input"))
    )
    (net (code "143") (name "unconnected-(U$5-ENC_CH_A-PadA)") (class "Default")
      (node (ref "U$5") (pin "A") (pinfunction "ENC_CH_A_A") (pintype "input"))
    )
    (net (code "144") (name "unconnected-(U$5-ENC_CH_A{slash}-PadA{slash})") (class "Default")
      (node (ref "U$5") (pin "A/") (pinfunction "ENC_CH_A/_A/") (pintype "input"))
    )
    (net (code "145") (name "unconnected-(U$5-ENC_CH_B-PadB)") (class "Default")
      (node (ref "U$5") (pin "B") (pinfunction "ENC_CH_B_B") (pintype "input"))
    )
    (net (code "146") (name "unconnected-(U$5-ENC_CH_B{slash}-PadB{slash})") (class "Default")
      (node (ref "U$5") (pin "B/") (pinfunction "ENC_CH_B/_B/") (pintype "input"))
    )
    (net (code "147") (name "unconnected-(U$5-PadA_IN1+)") (class "Default")
      (node (ref "U$5") (pin "A_IN1+") (pinfunction "A_IN1+_A_IN1+") (pintype "input"))
    )
    (net (code "148") (name "unconnected-(U$5-PadA_IN2+)") (class "Default")
      (node (ref "U$5") (pin "A_IN2+") (pinfunction "A_IN2+_A_IN2+") (pintype "input"))
    )
    (net (code "149") (name "unconnected-(U$5-PadA_OUT1)") (class "Default")
      (node (ref "U$5") (pin "A_OUT1") (pinfunction "A_OUT1_A_OUT1") (pintype "output"))
    )
    (net (code "150") (name "unconnected-(U$5-PadA_OUT2)") (class "Default")
      (node (ref "U$5") (pin "A_OUT2") (pinfunction "A_OUT2_A_OUT2") (pintype "output"))
    )
    (net (code "151") (name "unconnected-(U$5-PadD_IN{slash}D_OUT4)") (class "Default")
      (node (ref "U$5") (pin "D_IN/D_OUT4") (pinfunction "D_IN/D_OUT4_D_IN/D_OUT4") (pintype "bidirectional"))
    )
  )
)
